# wire_F.net
KiCad netlist of a schematic drawn in EAGLE
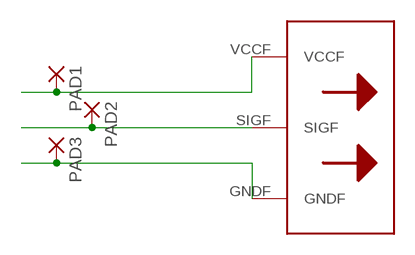
[diagram p0: schematic, sheet 1]

(export (version "E")
  (design (tool "Eeschema 10.0.6"))
  (components
    (comp (ref "PAD1")
      (value "SMD5")
      (footprint "eagle-import:SMD2,54-5,08")
      (libsource (lib "eagle-import") (part "SMD5"))
    )
    (comp (ref "PAD2")
      (value "SMD5")
      (footprint "eagle-import:SMD2,54-5,08")
      (libsource (lib "eagle-import") (part "SMD5"))
    )
    (comp (ref "PAD3")
      (value "SMD5")
      (footprint "eagle-import:SMD2,54-5,08")
      (libsource (lib "eagle-import") (part "SMD5"))
    )
    (comp (ref "U$2")
      (value "BITWIREF")
      (footprint "eagle-import:BITWIREF")
      (libsource (lib "eagle-import") (part "BITWIREF"))
    )
  )
  (nets
    (net (code "1") (name "Net-(PAD1-P)") (class "Default")
      (node (ref "PAD1") (pin "1") (pinfunction "P_1") (pintype "passive"))
      (node (ref "U$2") (pin "VCCF") (pinfunction "VCCF_VCCF") (pintype "bidirectional"))
    )
    (net (code "2") (name "Net-(PAD2-P)") (class "Default")
      (node (ref "PAD2") (pin "1") (pinfunction "P_1") (pintype "passive"))
      (node (ref "U$2") (pin "SIGF") (pinfunction "SIGF_SIGF") (pintype "bidirectional"))
    )
    (net (code "3") (name "Net-(PAD3-P)") (class "Default")
      (node (ref "PAD3") (pin "1") (pinfunction "P_1") (pintype "passive"))
      (node (ref "U$2") (pin "GNDF") (pinfunction "GNDF_GNDF") (pintype "bidirectional"))
    )
  )
)
